# RADG-Power-S02-V00.net
KiCad netlist of a schematic drawn in Altium Designer
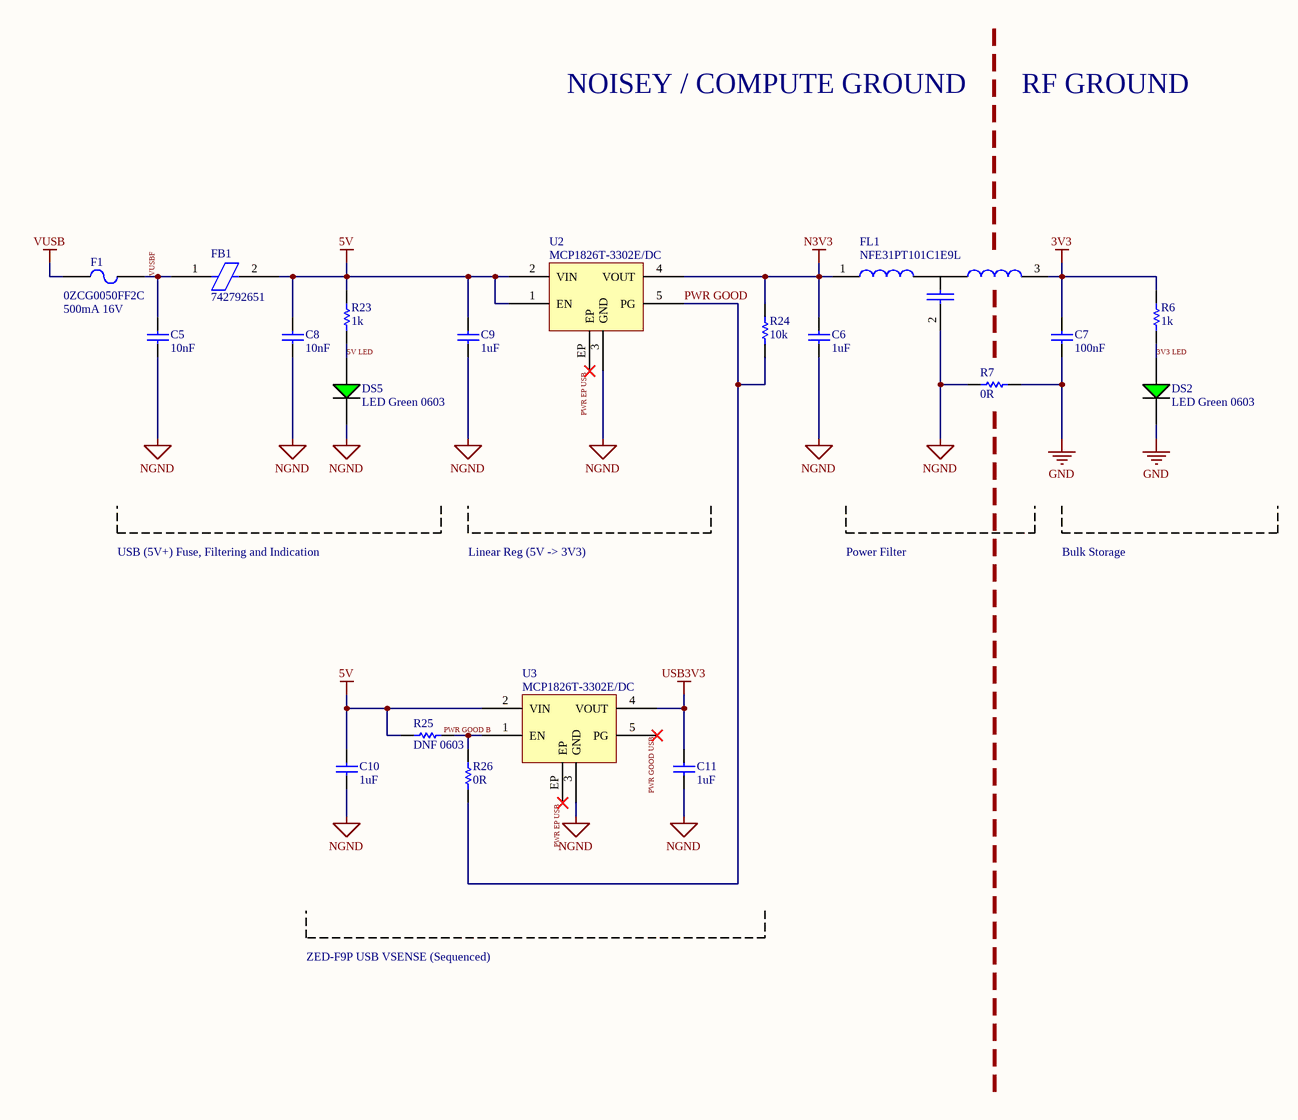
[diagram p0: RADG-Power-S02-V00.SchDoc]

(export (version "E")
  (design (tool "Eeschema 10.0.6"))
  (components
    (comp (ref "C5")
      (value "10nF")
      (footprint "Cap_Ceramic_0603")
      (description "Capacitor, Ceramic, SMD, 10nF, 50V, 5%, X7R, 0603")
      (libsource (lib "StandardCapacitors") (part "10nF 50V 5% X7R 0603"))
    )
    (comp (ref "C6")
      (value "1uF")
      (footprint "Cap_Ceramic_0603")
      (description "Capacitor, Ceramic, SMD, 1uF, 25V, 5%, X7R, 0603")
      (libsource (lib "StandardCapacitors") (part "1uF 25V 5% X7R 0603"))
    )
    (comp (ref "C7")
      (value "100nF")
      (footprint "Cap_Ceramic_0603")
      (description "Capacitor, Ceramic, SMD, 100nF, 50V, 5%, X7R, 0603")
      (libsource (lib "StandardCapacitors") (part "100nF 50V 5% X7R 0603"))
    )
    (comp (ref "C8")
      (value "10nF")
      (footprint "Cap_Ceramic_0603")
      (description "Capacitor, Ceramic, SMD, 10nF, 50V, 5%, X7R, 0603")
      (libsource (lib "StandardCapacitors") (part "10nF 50V 5% X7R 0603"))
    )
    (comp (ref "C9")
      (value "1uF")
      (footprint "Cap_Ceramic_0603")
      (description "Capacitor, Ceramic, SMD, 1uF, 25V, 5%, X7R, 0603")
      (libsource (lib "StandardCapacitors") (part "1uF 25V 5% X7R 0603"))
    )
    (comp (ref "C10")
      (value "1uF")
      (footprint "Cap_Ceramic_0603")
      (description "Capacitor, Ceramic, SMD, 1uF, 25V, 5%, X7R, 0603")
      (libsource (lib "StandardCapacitors") (part "1uF 25V 5% X7R 0603"))
    )
    (comp (ref "C11")
      (value "1uF")
      (footprint "Cap_Ceramic_0603")
      (description "Capacitor, Ceramic, SMD, 1uF, 25V, 5%, X7R, 0603")
      (libsource (lib "StandardCapacitors") (part "1uF 25V 5% X7R 0603"))
    )
    (comp (ref "DS2")
      (value "LED Green 0603")
      (footprint "LED GREEN 0603")
      (libsource (lib "QUTMS_LEDLibrary") (part "LED Green 0603"))
    )
    (comp (ref "DS5")
      (value "LED Green 0603")
      (footprint "LED GREEN 0603")
      (libsource (lib "QUTMS_LEDLibrary") (part "LED Green 0603"))
    )
    (comp (ref "F1")
      (value "0ZCG0050FF2C")
      (footprint "1812 FUSE")
      (description "Polymeric PTC Resettable Fuse 16V 500mA Ih Surface Mount 1812 (4532 Metric), Concave")
      (libsource (lib "QUTMS_FuseLibrary") (part "0ZCG0050FF2C"))
    )
    (comp (ref "FB1")
      (value "742792651")
      (footprint "Inductor_0603")
      (description "600 Ohms @ 100MHz 1 Signal Line Ferrite Bead 0603 (1608 Metric) 1A 200mOhm")
      (libsource (lib "QUTMS_InductorLibrary") (part "742792651"))
    )
    (comp (ref "FL1")
      (value "NFE31PT101C1E9L")
      (footprint "NFE31PT101C1E9L")
      (description "LC (T-Type) EMI Filter 3rd Order Low Pass 1 Channel C = 100pF 6A 1206 (3216 Metric), 3 PC Pad")
      (libsource (lib "QUTMS_PowerSupplyLibrary") (part "NFE31PT101C1E9L"))
    )
    (comp (ref "R6")
      (value "1k")
      (footprint "Res_ThinFilm_0603")
      (description "Resistor, SMD, 1k, 0.1W, 5%, 0603")
      (libsource (lib "StandardResistors") (part "1k 5% 0603"))
    )
    (comp (ref "R7")
      (value "0R")
      (footprint "Res_ThinFilm_0603")
      (description "Resistor, SMD, 0R, 0.1W, 5%, 0603")
      (libsource (lib "StandardResistors") (part "0R 5% 0603"))
    )
    (comp (ref "R23")
      (value "1k")
      (footprint "Res_ThinFilm_0603")
      (description "Resistor, SMD, 1k, 0.1W, 5%, 0603")
      (libsource (lib "StandardResistors") (part "1k 5% 0603"))
    )
    (comp (ref "R24")
      (value "10k")
      (footprint "Res_ThinFilm_0603")
      (description "Resistor, SMD, 10k, 0.1W, 5%, 0603")
      (libsource (lib "StandardResistors") (part "10k 5% 0603"))
    )
    (comp (ref "R25")
      (value "DNF 0603")
      (footprint "Res_ThinFilm_0603")
      (description "Resistor, SMD, DNF, 0.1W, 0603")
      (libsource (lib "StandardResistors") (part "DNF 0603"))
    )
    (comp (ref "R26")
      (value "0R")
      (footprint "Res_ThinFilm_0603")
      (description "Resistor, SMD, 0R, 0.1W, 5%, 0603")
      (libsource (lib "StandardResistors") (part "0R 5% 0603"))
    )
    (comp (ref "U2")
      (value "MCP1826T-3302E/DC")
      (footprint "SOT-223-5")
      (description "Linear Voltage Regulator IC Positive Fixed 1 Output 1A SOT-223-5")
      (libsource (lib "QUTMS_PowerSupplyLibrary") (part "MCP1826T-3302E/DC"))
    )
    (comp (ref "U3")
      (value "MCP1826T-3302E/DC")
      (footprint "SOT-223-5")
      (description "Linear Voltage Regulator IC Positive Fixed 1 Output 1A SOT-223-5")
      (libsource (lib "QUTMS_PowerSupplyLibrary") (part "MCP1826T-3302E/DC"))
    )
  )
  (nets
    (net (code "1") (name "/3V3 LED") (class "Default")
      (node (ref "DS2") (pin "1") (pinfunction "A_1") (pintype "passive"))
      (node (ref "R6") (pin "1") (pinfunction "1_1") (pintype "passive"))
    )
    (net (code "2") (name "/5V LED") (class "Default")
      (node (ref "DS5") (pin "1") (pinfunction "A_1") (pintype "passive"))
      (node (ref "R23") (pin "1") (pinfunction "1_1") (pintype "passive"))
    )
    (net (code "3") (name "/PWR EP USB") (class "Default")
      (node (ref "U2") (pin "EP") (pinfunction "EP_EP") (pintype "passive"))
      (node (ref "U3") (pin "EP") (pinfunction "EP_EP") (pintype "passive"))
    )
    (net (code "4") (name "/PWR GOOD") (class "Default")
      (node (ref "R24") (pin "1") (pinfunction "1_1") (pintype "passive"))
      (node (ref "R26") (pin "1") (pinfunction "1_1") (pintype "passive"))
      (node (ref "U2") (pin "5") (pinfunction "PG_5") (pintype "passive"))
    )
    (net (code "5") (name "/PWR GOOD B") (class "Default")
      (node (ref "R25") (pin "2") (pinfunction "2_2") (pintype "passive"))
      (node (ref "R26") (pin "2") (pinfunction "2_2") (pintype "passive"))
      (node (ref "U3") (pin "1") (pinfunction "EN_1") (pintype "passive"))
    )
    (net (code "6") (name "/PWR GOOD USB") (class "Default")
      (node (ref "U3") (pin "5") (pinfunction "PG_5") (pintype "passive+no_connect"))
    )
    (net (code "7") (name "/VUSBF") (class "Default")
      (node (ref "C5") (pin "2") (pinfunction "2_2") (pintype "passive"))
      (node (ref "F1") (pin "2") (pinfunction "2_2") (pintype "passive"))
      (node (ref "FB1") (pin "1") (pinfunction "1_1") (pintype "passive"))
    )
    (net (code "8") (name "3V3") (class "Default")
      (node (ref "C7") (pin "2") (pinfunction "2_2") (pintype "passive"))
      (node (ref "FL1") (pin "3") (pinfunction "3_3") (pintype "passive"))
      (node (ref "R6") (pin "2") (pinfunction "2_2") (pintype "passive"))
    )
    (net (code "9") (name "5V") (class "Default")
      (node (ref "C10") (pin "2") (pinfunction "2_2") (pintype "passive"))
      (node (ref "C8") (pin "2") (pinfunction "2_2") (pintype "passive"))
      (node (ref "C9") (pin "2") (pinfunction "2_2") (pintype "passive"))
      (node (ref "FB1") (pin "2") (pinfunction "2_2") (pintype "passive"))
      (node (ref "R23") (pin "2") (pinfunction "2_2") (pintype "passive"))
      (node (ref "R25") (pin "1") (pinfunction "1_1") (pintype "passive"))
      (node (ref "U2") (pin "1") (pinfunction "EN_1") (pintype "passive"))
      (node (ref "U2") (pin "2") (pinfunction "VIN_2") (pintype "passive"))
      (node (ref "U3") (pin "2") (pinfunction "VIN_2") (pintype "passive"))
    )
    (net (code "10") (name "GND") (class "Default")
      (node (ref "C7") (pin "1") (pinfunction "1_1") (pintype "passive"))
      (node (ref "DS2") (pin "2") (pinfunction "C_2") (pintype "passive"))
      (node (ref "R7") (pin "2") (pinfunction "2_2") (pintype "passive"))
    )
    (net (code "11") (name "N3V3") (class "Default")
      (node (ref "C6") (pin "2") (pinfunction "2_2") (pintype "passive"))
      (node (ref "FL1") (pin "1") (pinfunction "1_1") (pintype "passive"))
      (node (ref "R24") (pin "2") (pinfunction "2_2") (pintype "passive"))
      (node (ref "U2") (pin "4") (pinfunction "VOUT_4") (pintype "passive"))
    )
    (net (code "12") (name "NGND") (class "Default")
      (node (ref "C10") (pin "1") (pinfunction "1_1") (pintype "passive"))
      (node (ref "C11") (pin "1") (pinfunction "1_1") (pintype "passive"))
      (node (ref "C5") (pin "1") (pinfunction "1_1") (pintype "passive"))
      (node (ref "C6") (pin "1") (pinfunction "1_1") (pintype "passive"))
      (node (ref "C8") (pin "1") (pinfunction "1_1") (pintype "passive"))
      (node (ref "C9") (pin "1") (pinfunction "1_1") (pintype "passive"))
      (node (ref "DS5") (pin "2") (pinfunction "C_2") (pintype "passive"))
      (node (ref "FL1") (pin "2") (pinfunction "2_2") (pintype "passive"))
      (node (ref "R7") (pin "1") (pinfunction "1_1") (pintype "passive"))
      (node (ref "U2") (pin "3") (pinfunction "GND_3") (pintype "passive"))
      (node (ref "U3") (pin "3") (pinfunction "GND_3") (pintype "passive"))
    )
    (net (code "13") (name "USB3V3") (class "Default")
      (node (ref "C11") (pin "2") (pinfunction "2_2") (pintype "passive"))
      (node (ref "U3") (pin "4") (pinfunction "VOUT_4") (pintype "passive"))
    )
    (net (code "14") (name "VUSB") (class "Default")
      (node (ref "F1") (pin "1") (pinfunction "1_1") (pintype "passive"))
    )
  )
)
